# CCD.net
KiCad netlist of a schematic drawn in Altium Designer
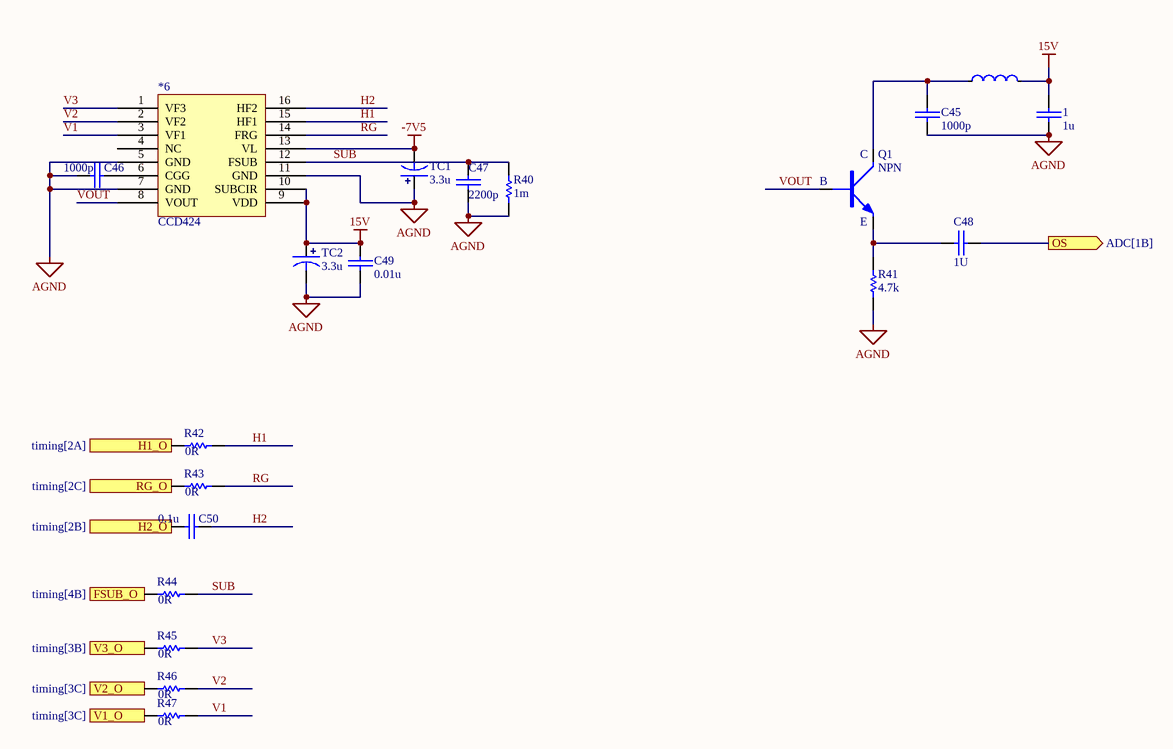
[diagram p0: CCD.SchDoc]

(export (version "E")
  (design (tool "Eeschema 10.0.6"))
  (components
    (comp (ref "*6") (value "CCD424") (footprint "CCD424") (libsource (lib "0.01-CCD") (part "CCD424")))
    (comp (ref "1")
      (value "1u")
      (footprint "0603C")
      (description "无极性电容")
      (libsource (lib "1.00-阻容感") (part "CAP"))
    )
    (comp (ref "C45")
      (value "1000p")
      (footprint "0603C")
      (description "无极性电容")
      (libsource (lib "1.00-阻容感") (part "CAP"))
    )
    (comp (ref "C46")
      (value "1000p")
      (footprint "0603C")
      (description "无极性电容")
      (libsource (lib "1.00-阻容感") (part "CAP"))
    )
    (comp (ref "C47")
      (value "2200p")
      (footprint "0603C")
      (description "无极性电容")
      (libsource (lib "1.00-阻容感") (part "CAP"))
    )
    (comp (ref "C48")
      (value "1U")
      (footprint "0603C")
      (description "无极性电容")
      (libsource (lib "1.00-阻容感") (part "CAP"))
    )
    (comp (ref "C49")
      (value "0.01u")
      (footprint "0603C")
      (description "无极性电容")
      (libsource (lib "1.00-阻容感") (part "CAP"))
    )
    (comp (ref "C50")
      (value "0.1u")
      (footprint "0603C")
      (description "无极性电容")
      (libsource (lib "1.00-阻容感") (part "CAP"))
    )
    (comp (ref "L13")
      (value "GZ1608D601TF")
      (footprint "0603L")
      (description "铁氧体磁珠")
      (fields (field (name "MANUFACTURER") "Sunlord(顺络)") (field (name "TOLERANCE") "±25%"))
      (libsource (lib "1.00-阻容感") (part "FB"))
    )
    (comp (ref "Q1")
      (value "NPN")
      (footprint "SOT23-3")
      (description "NPN三极管")
      (libsource (lib "3.02-三极管") (part "NPN"))
    )
    (comp (ref "R40")
      (value "1m")
      (footprint "0603R")
      (description "电阻")
      (libsource (lib "1.00-阻容感") (part "RES"))
    )
    (comp (ref "R41")
      (value "4.7k")
      (footprint "0603R")
      (description "电阻")
      (libsource (lib "1.00-阻容感") (part "RES"))
    )
    (comp (ref "R42")
      (value "0R")
      (footprint "0603R")
      (description "电阻")
      (libsource (lib "1.00-阻容感") (part "RES"))
    )
    (comp (ref "R43")
      (value "0R")
      (footprint "0603R")
      (description "电阻")
      (libsource (lib "1.00-阻容感") (part "RES"))
    )
    (comp (ref "R44")
      (value "0R")
      (footprint "0603R")
      (description "电阻")
      (libsource (lib "1.00-阻容感") (part "RES"))
    )
    (comp (ref "R45")
      (value "0R")
      (footprint "0603R")
      (description "电阻")
      (libsource (lib "1.00-阻容感") (part "RES"))
    )
    (comp (ref "R46")
      (value "0R")
      (footprint "0603R")
      (description "电阻")
      (libsource (lib "1.00-阻容感") (part "RES"))
    )
    (comp (ref "R47")
      (value "0R")
      (footprint "0603R")
      (description "电阻")
      (libsource (lib "1.00-阻容感") (part "RES"))
    )
    (comp (ref "TC1")
      (value "3.3u")
      (footprint "TAJ-A/3216")
      (description "钽电容")
      (libsource (lib "1.00-阻容感") (part "TCAP"))
    )
    (comp (ref "TC2")
      (value "3.3u")
      (footprint "TAJ-A/3216")
      (description "钽电容")
      (libsource (lib "1.00-阻容感") (part "TCAP"))
    )
  )
  (nets
    (net (code "1") (name "-7V5") (class "Default")
      (node (ref "*6") (pin "13") (pinfunction "VL_13") (pintype "passive"))
      (node (ref "TC1") (pin "2") (pinfunction "2_2") (pintype "passive"))
    )
    (net (code "2") (name "/FSUB_O") (class "Default")
      (node (ref "R44") (pin "2") (pinfunction "2_2") (pintype "passive"))
    )
    (net (code "3") (name "/H1") (class "Default")
      (node (ref "*6") (pin "15") (pinfunction "HF1_15") (pintype "passive"))
      (node (ref "R42") (pin "1") (pinfunction "1_1") (pintype "passive"))
    )
    (net (code "4") (name "/H1_O") (class "Default")
      (node (ref "R42") (pin "2") (pinfunction "2_2") (pintype "passive"))
    )
    (net (code "5") (name "/H2") (class "Default")
      (node (ref "*6") (pin "16") (pinfunction "HF2_16") (pintype "passive"))
      (node (ref "C50") (pin "1") (pinfunction "1_1") (pintype "passive"))
    )
    (net (code "6") (name "/H2_O") (class "Default")
      (node (ref "C50") (pin "2") (pinfunction "2_2") (pintype "passive"))
    )
    (net (code "7") (name "/OS") (class "Default")
      (node (ref "C48") (pin "1") (pinfunction "1_1") (pintype "passive"))
    )
    (net (code "8") (name "/RG") (class "Default")
      (node (ref "*6") (pin "14") (pinfunction "FRG_14") (pintype "passive"))
      (node (ref "R43") (pin "1") (pinfunction "1_1") (pintype "passive"))
    )
    (net (code "9") (name "/RG_O") (class "Default")
      (node (ref "R43") (pin "2") (pinfunction "2_2") (pintype "passive"))
    )
    (net (code "10") (name "/SUB") (class "Default")
      (node (ref "*6") (pin "12") (pinfunction "FSUB_12") (pintype "passive"))
      (node (ref "C47") (pin "2") (pinfunction "2_2") (pintype "passive"))
      (node (ref "R40") (pin "2") (pinfunction "2_2") (pintype "passive"))
      (node (ref "R44") (pin "1") (pinfunction "1_1") (pintype "passive"))
    )
    (net (code "11") (name "/V1") (class "Default")
      (node (ref "*6") (pin "3") (pinfunction "VF1_3") (pintype "passive"))
      (node (ref "R47") (pin "1") (pinfunction "1_1") (pintype "passive"))
    )
    (net (code "12") (name "/V1_O") (class "Default")
      (node (ref "R47") (pin "2") (pinfunction "2_2") (pintype "passive"))
    )
    (net (code "13") (name "/V2") (class "Default")
      (node (ref "*6") (pin "2") (pinfunction "VF2_2") (pintype "passive"))
      (node (ref "R46") (pin "1") (pinfunction "1_1") (pintype "passive"))
    )
    (net (code "14") (name "/V2_O") (class "Default")
      (node (ref "R46") (pin "2") (pinfunction "2_2") (pintype "passive"))
    )
    (net (code "15") (name "/V3") (class "Default")
      (node (ref "*6") (pin "1") (pinfunction "VF3_1") (pintype "passive"))
      (node (ref "R45") (pin "1") (pinfunction "1_1") (pintype "passive"))
    )
    (net (code "16") (name "/V3_O") (class "Default")
      (node (ref "R45") (pin "2") (pinfunction "2_2") (pintype "passive"))
    )
    (net (code "17") (name "/VOUT") (class "Default")
      (node (ref "*6") (pin "8") (pinfunction "VOUT_8") (pintype "passive"))
      (node (ref "Q1") (pin "1") (pinfunction "B_1") (pintype "passive"))
    )
    (net (code "18") (name "15V") (class "Default")
      (node (ref "*6") (pin "10") (pinfunction "SUBCIR_10") (pintype "passive"))
      (node (ref "*6") (pin "9") (pinfunction "VDD_9") (pintype "passive"))
      (node (ref "1") (pin "2") (pinfunction "2_2") (pintype "passive"))
      (node (ref "C49") (pin "2") (pinfunction "2_2") (pintype "passive"))
      (node (ref "L13") (pin "2") (pinfunction "2_2") (pintype "passive"))
      (node (ref "TC2") (pin "1") (pinfunction "1_1") (pintype "passive"))
    )
    (net (code "19") (name "AGND") (class "Default")
      (node (ref "*6") (pin "11") (pinfunction "GND_11") (pintype "passive"))
      (node (ref "*6") (pin "5") (pinfunction "GND_5") (pintype "passive"))
      (node (ref "*6") (pin "7") (pinfunction "GND_7") (pintype "passive"))
      (node (ref "1") (pin "1") (pinfunction "1_1") (pintype "passive"))
      (node (ref "C45") (pin "1") (pinfunction "1_1") (pintype "passive"))
      (node (ref "C46") (pin "2") (pinfunction "2_2") (pintype "passive"))
      (node (ref "C47") (pin "1") (pinfunction "1_1") (pintype "passive"))
      (node (ref "C49") (pin "1") (pinfunction "1_1") (pintype "passive"))
      (node (ref "R40") (pin "1") (pinfunction "1_1") (pintype "passive"))
      (node (ref "R41") (pin "1") (pinfunction "1_1") (pintype "passive"))
      (node (ref "TC1") (pin "1") (pinfunction "1_1") (pintype "passive"))
      (node (ref "TC2") (pin "2") (pinfunction "2_2") (pintype "passive"))
    )
    (net (code "20") (name "Net-(*6-CGG)") (class "Default")
      (node (ref "*6") (pin "6") (pinfunction "CGG_6") (pintype "passive"))
      (node (ref "C46") (pin "1") (pinfunction "1_1") (pintype "passive"))
    )
    (net (code "21") (name "Net-(Q1-C)") (class "Default")
      (node (ref "C45") (pin "2") (pinfunction "2_2") (pintype "passive"))
      (node (ref "L13") (pin "1") (pinfunction "1_1") (pintype "passive"))
      (node (ref "Q1") (pin "3") (pinfunction "C_3") (pintype "passive"))
    )
    (net (code "22") (name "Net-(Q1-E)") (class "Default")
      (node (ref "C48") (pin "2") (pinfunction "2_2") (pintype "passive"))
      (node (ref "Q1") (pin "2") (pinfunction "E_2") (pintype "passive"))
      (node (ref "R41") (pin "2") (pinfunction "2_2") (pintype "passive"))
    )
    (net (code "23") (name "unconnected-(*6-NC-Pad4)") (class "Default")
      (node (ref "*6") (pin "4") (pinfunction "NC_4") (pintype "passive"))
    )
  )
)
